# Audio.net
KiCad netlist of a schematic drawn in Altium Designer
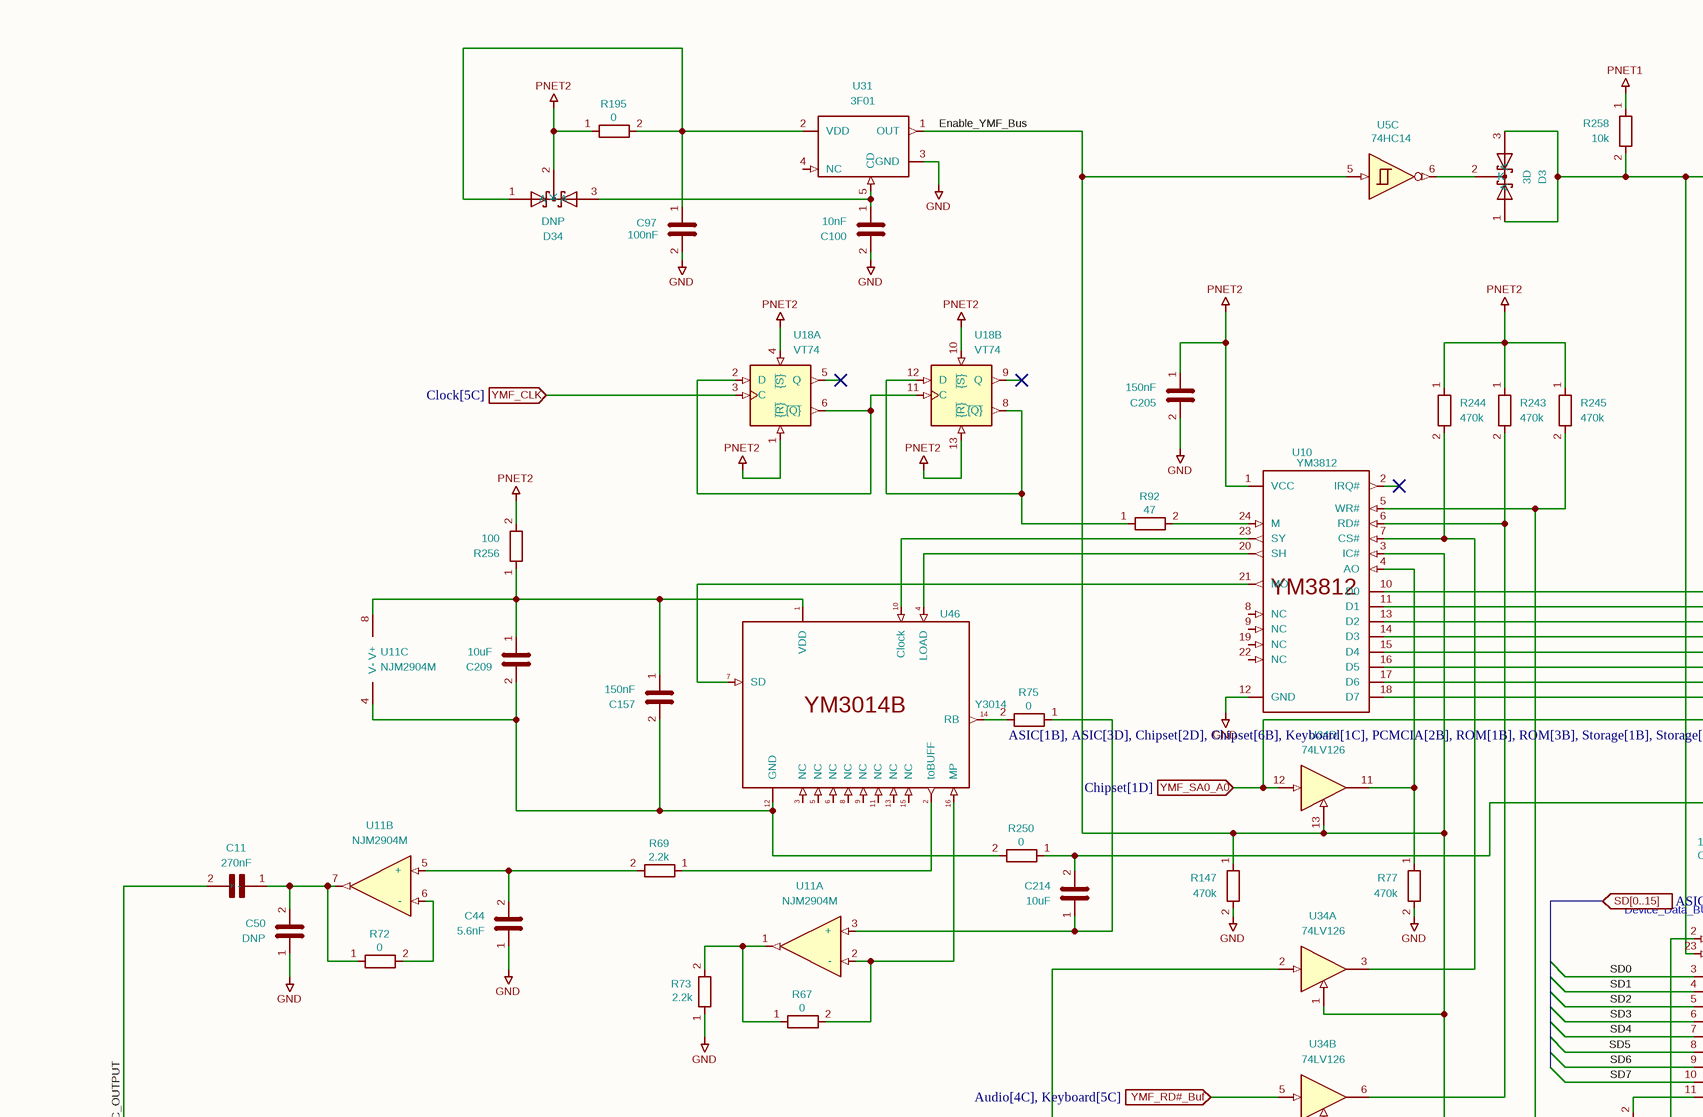
[diagram p0: Audio.SchDoc, top left]
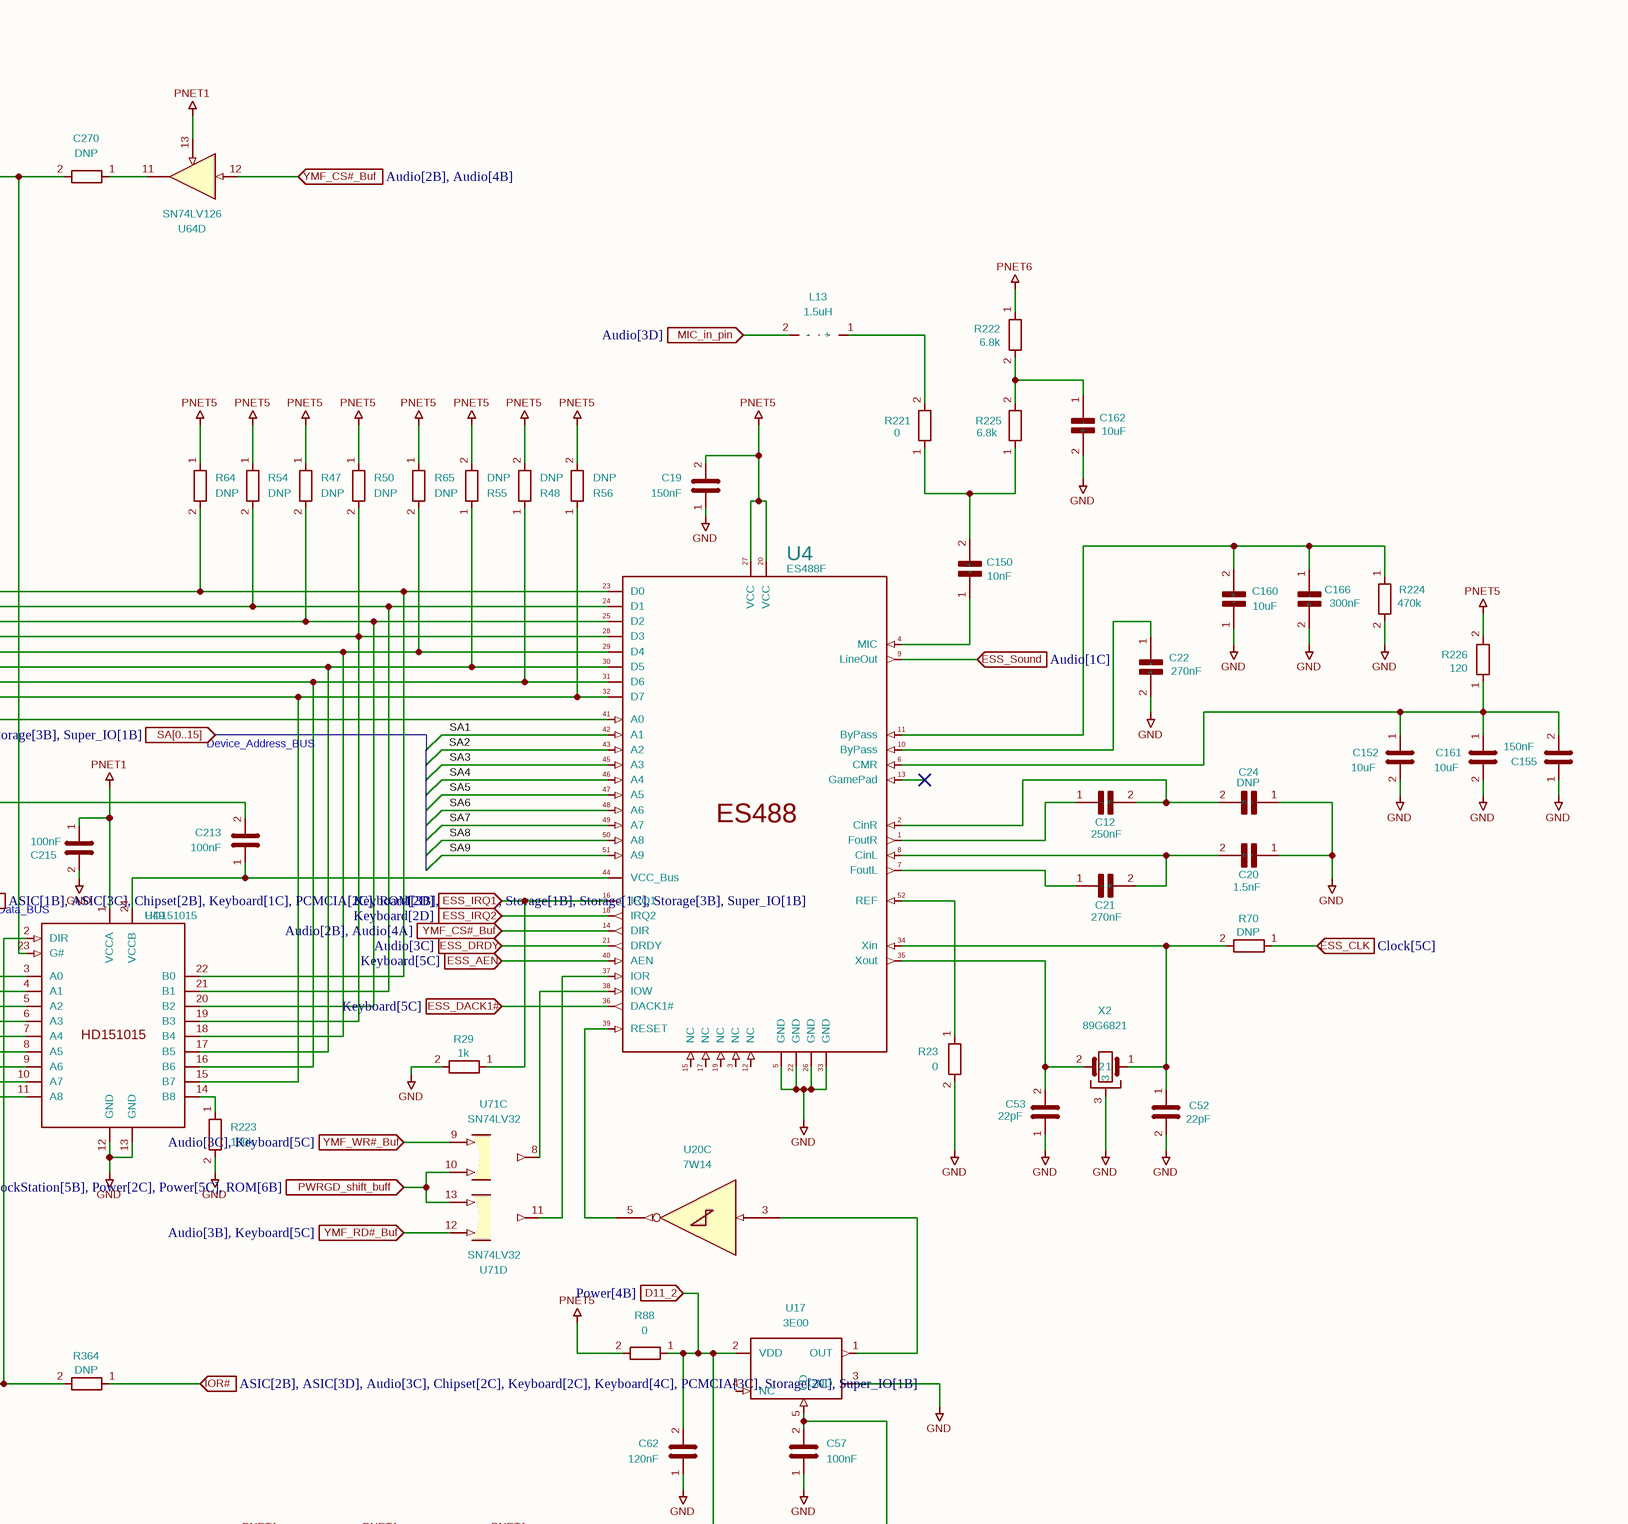
[diagram p1: Audio.SchDoc, top right]
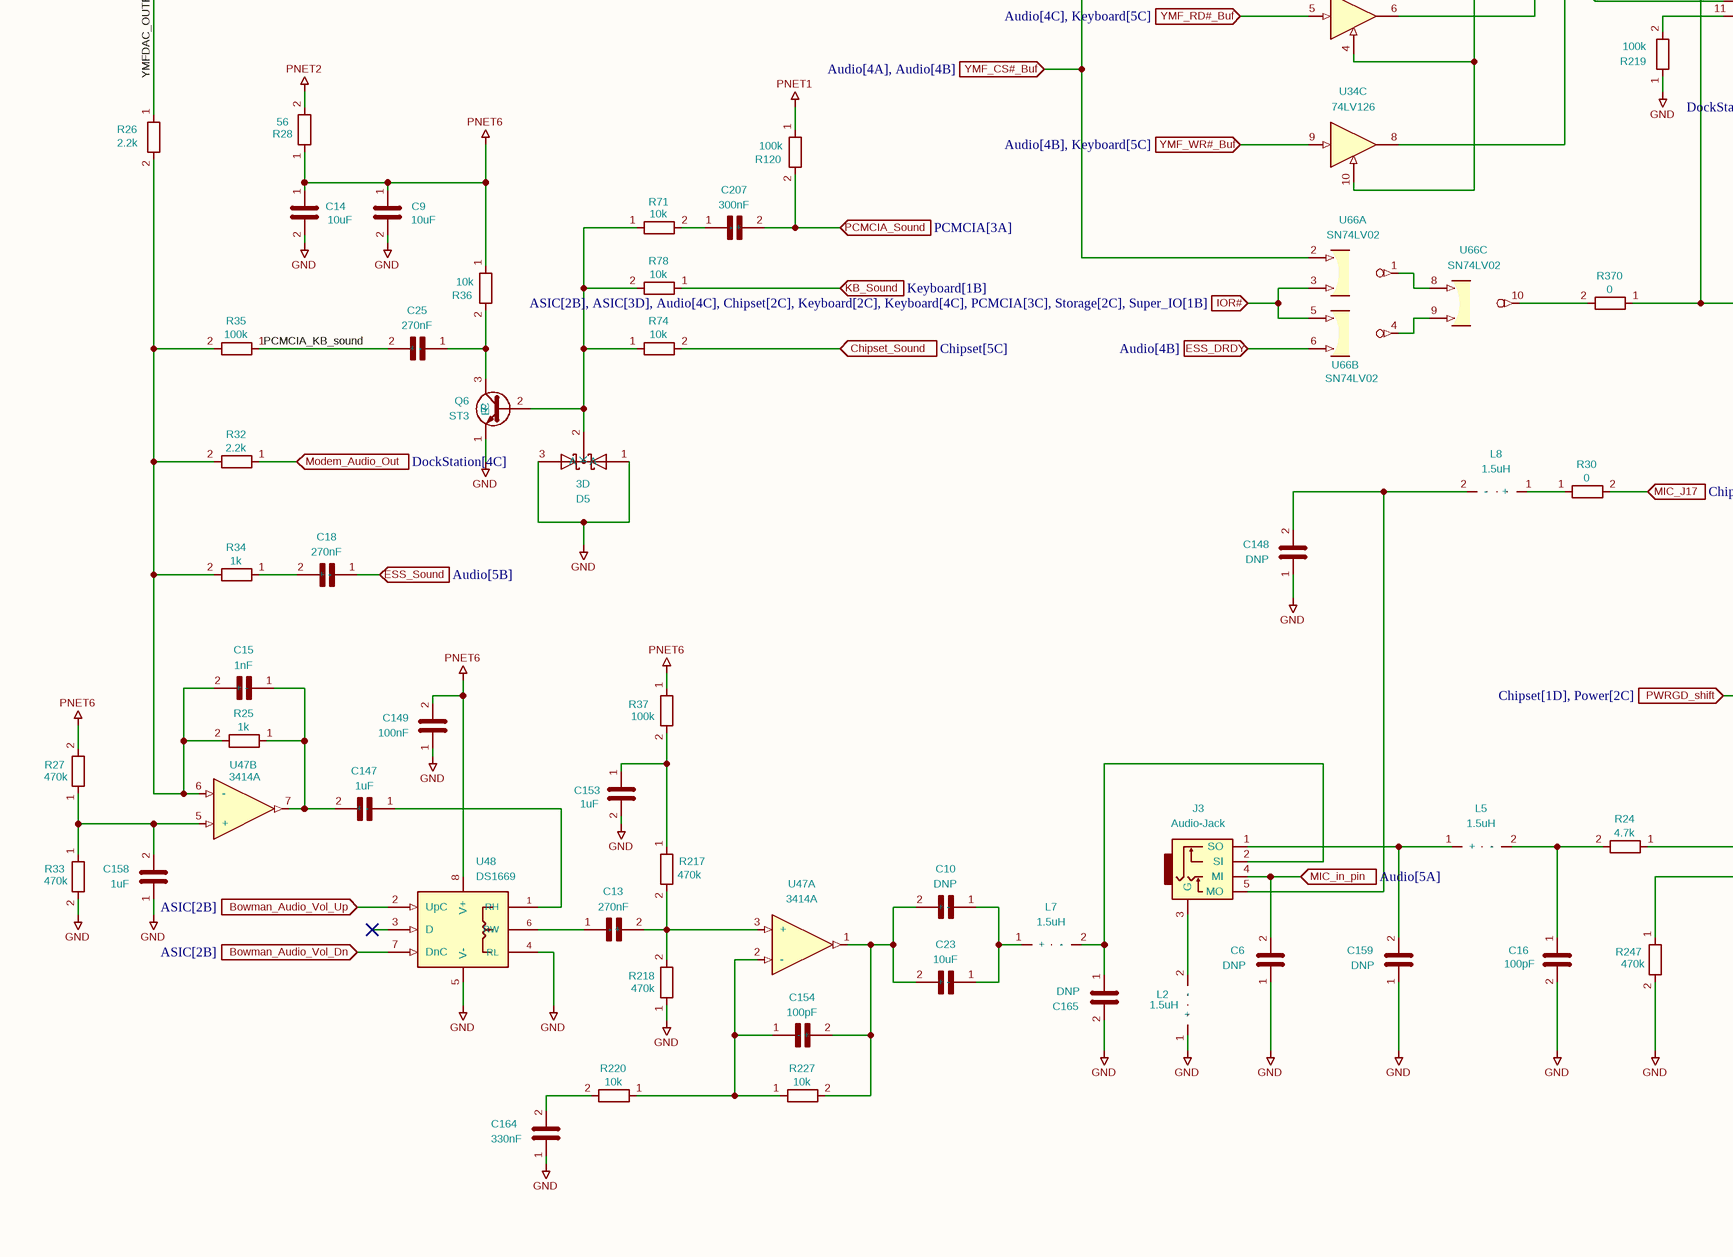
[diagram p2: Audio.SchDoc, bottom left]
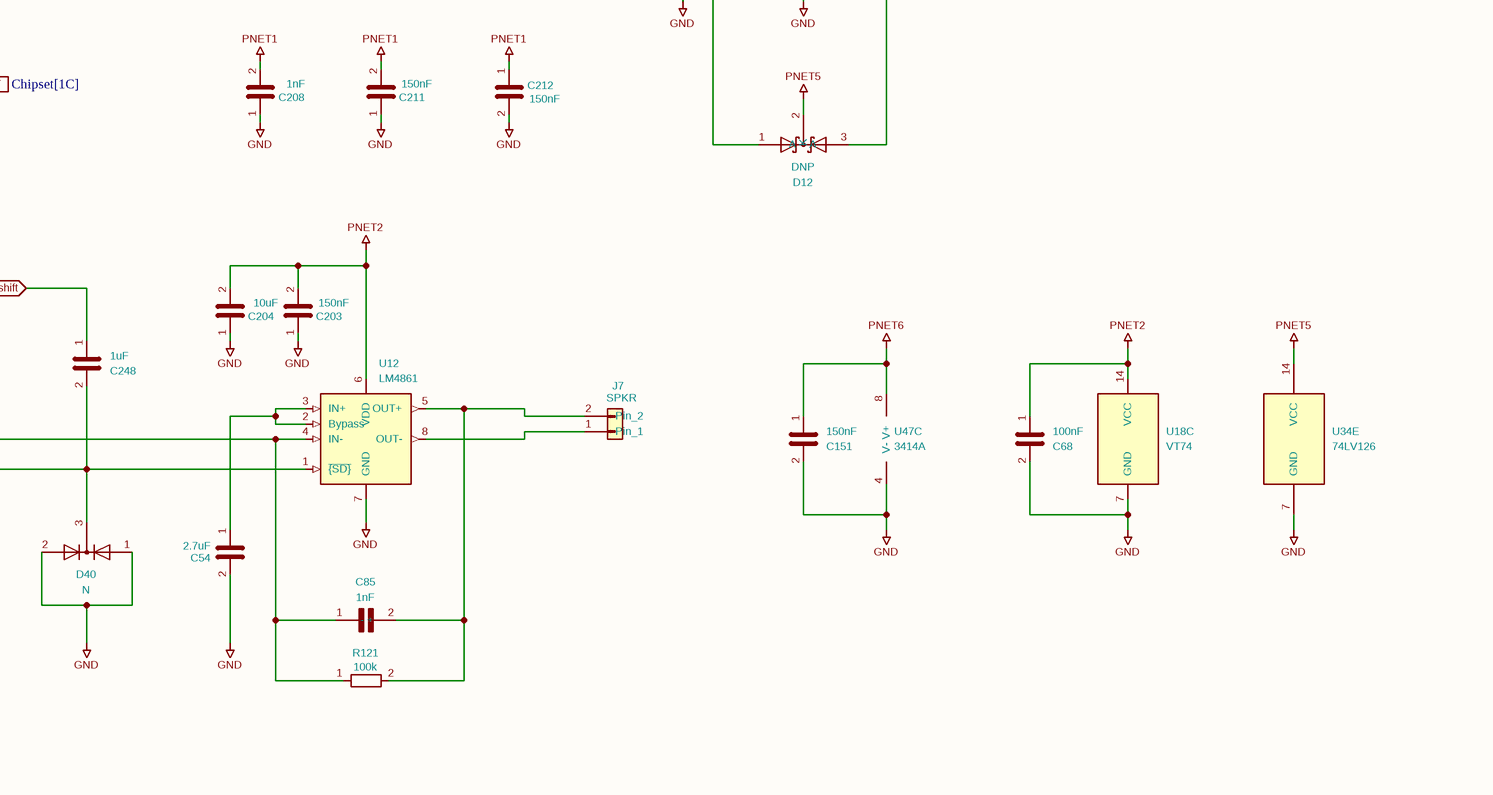
[diagram p3: Audio.SchDoc, bottom right]

(export (version "E")
  (design (tool "Eeschema 10.0.6"))
  (components
    (comp (ref "C6") (value "DNP") (footprint "C_0402_1005Metric") (libsource (lib "Device") (part "C")))
    (comp (ref "C9") (value "10uF") (footprint "C_1206_3216Metric") (libsource (lib "Device") (part "C")))
    (comp (ref "C10")
      (value "DNP")
      (footprint "C_1206_3216Metric")
      (libsource (lib "PCM_Elektuur") (part "C"))
    )
    (comp (ref "C11")
      (value "270nF")
      (footprint "C_0603_1608Metric")
      (libsource (lib "PCM_Elektuur") (part "C"))
    )
    (comp (ref "C12") (value "250nF") (footprint "C_0603_1608Metric") (libsource (lib "") (part "C_1")))
    (comp (ref "C13") (value "270nF") (footprint "C_0603_1608Metric") (libsource (lib "") (part "C_2")))
    (comp (ref "C14") (value "10uF") (footprint "C_1206_3216Metric") (libsource (lib "Device") (part "C")))
    (comp (ref "C15")
      (value "1nF")
      (footprint "C_0402_1005Metric")
      (libsource (lib "PCM_Elektuur") (part "C"))
    )
    (comp (ref "C16") (value "100pF") (footprint "C_0402_1005Metric") (libsource (lib "Device") (part "C")))
    (comp (ref "C18")
      (value "270nF")
      (footprint "C_0603_1608Metric")
      (libsource (lib "PCM_Elektuur") (part "C"))
    )
    (comp (ref "C19") (value "150nF") (footprint "C_0402_1005Metric") (libsource (lib "Device") (part "C")))
    (comp (ref "C20") (value "1.5nF") (footprint "C_0402_1005Metric") (libsource (lib "") (part "C_3")))
    (comp (ref "C21") (value "270nF") (footprint "C_0603_1608Metric") (libsource (lib "") (part "C_1")))
    (comp (ref "C22")
      (value "270nF")
      (footprint "C_0603_1608Metric")
      (libsource (lib "PCM_Elektuur") (part "C"))
    )
    (comp (ref "C23")
      (value "10uF")
      (footprint "C_1206_3216Metric")
      (libsource (lib "PCM_Elektuur") (part "C"))
    )
    (comp (ref "C24")
      (value "DNP")
      (footprint "C_0402_1005Metric")
      (libsource (lib "PCM_Elektuur") (part "C"))
    )
    (comp (ref "C25")
      (value "270nF")
      (footprint "C_0603_1608Metric")
      (libsource (lib "PCM_Elektuur") (part "C"))
    )
    (comp (ref "C44") (value "5.6nF") (footprint "C_0402_1005Metric") (libsource (lib "Device") (part "C")))
    (comp (ref "C50") (value "DNP") (footprint "C_0402_1005Metric") (libsource (lib "Device") (part "C")))
    (comp (ref "C52") (value "22pF") (footprint "C_0402_1005Metric") (libsource (lib "Device") (part "C")))
    (comp (ref "C53") (value "22pF") (footprint "C_0402_1005Metric") (libsource (lib "Device") (part "C")))
    (comp (ref "C54") (value "2.7uF") (footprint "C_0805_2012Metric") (libsource (lib "Device") (part "C")))
    (comp (ref "C57") (value "100nF") (footprint "C_0603_1608Metric") (libsource (lib "Device") (part "C")))
    (comp (ref "C62") (value "120nF") (footprint "C_0402_1005Metric") (libsource (lib "Device") (part "C")))
    (comp (ref "C68") (value "100nF") (footprint "C_0402_1005Metric") (libsource (lib "Device") (part "C")))
    (comp (ref "C85") (value "1nF") (footprint "C_0402_1005Metric") (libsource (lib "") (part "C_2")))
    (comp (ref "C97") (value "100nF") (footprint "C_0402_1005Metric") (libsource (lib "Device") (part "C")))
    (comp (ref "C100") (value "10nF") (footprint "C_0603_1608Metric") (libsource (lib "Device") (part "C")))
    (comp (ref "C147")
      (value "1uF")
      (footprint "C_0603_1608Metric")
      (libsource (lib "PCM_Elektuur") (part "C"))
    )
    (comp (ref "C148") (value "DNP") (footprint "C_0402_1005Metric") (libsource (lib "Device") (part "C")))
    (comp (ref "C149") (value "100nF") (footprint "C_0402_1005Metric") (libsource (lib "Device") (part "C")))
    (comp (ref "C150") (value "10nF") (footprint "C_0603_1608Metric") (libsource (lib "") (part "C_2")))
    (comp (ref "C151") (value "150nF") (footprint "C_0402_1005Metric") (libsource (lib "Device") (part "C")))
    (comp (ref "C152") (value "10uF") (footprint "C_1206_3216Metric") (libsource (lib "Device") (part "C")))
    (comp (ref "C153") (value "1uF") (footprint "C_0603_1608Metric") (libsource (lib "Device") (part "C")))
    (comp (ref "C154") (value "100pF") (footprint "C_0402_1005Metric") (libsource (lib "") (part "C_2")))
    (comp (ref "C155") (value "150nF") (footprint "C_0402_1005Metric") (libsource (lib "Device") (part "C")))
    (comp (ref "C157") (value "150nF") (footprint "C_0402_1005Metric") (libsource (lib "Device") (part "C")))
    (comp (ref "C158") (value "1uF") (footprint "C_0603_1608Metric") (libsource (lib "Device") (part "C")))
    (comp (ref "C159") (value "DNP") (footprint "C_0402_1005Metric") (libsource (lib "Device") (part "C")))
    (comp (ref "C160") (value "10uF") (footprint "C_1206_3216Metric") (libsource (lib "") (part "C_2")))
    (comp (ref "C161") (value "10uF") (footprint "C_1206_3216Metric") (libsource (lib "Device") (part "C")))
    (comp (ref "C162")
      (value "10uF")
      (footprint "C_1206_3216Metric")
      (libsource (lib "PCM_Elektuur") (part "C"))
    )
    (comp (ref "C164") (value "330nF") (footprint "C_0603_1608Metric") (libsource (lib "Device") (part "C")))
    (comp (ref "C165") (value "DNP") (footprint "C_0402_1005Metric") (libsource (lib "Device") (part "C")))
    (comp (ref "C166")
      (value "300nF")
      (footprint "C_0603_1608Metric")
      (libsource (lib "PCM_Elektuur") (part "C"))
    )
    (comp (ref "C203") (value "150nF") (footprint "C_0402_1005Metric") (libsource (lib "Device") (part "C")))
    (comp (ref "C204") (value "10uF") (footprint "C_1206_3216Metric") (libsource (lib "Device") (part "C")))
    (comp (ref "C205") (value "150nF") (footprint "C_0402_1005Metric") (libsource (lib "Device") (part "C")))
    (comp (ref "C207") (value "300nF") (footprint "C_0603_1608Metric") (libsource (lib "") (part "C_2")))
    (comp (ref "C208") (value "1nF") (footprint "C_0402_1005Metric") (libsource (lib "Device") (part "C")))
    (comp (ref "C209") (value "10uF") (footprint "C_1206_3216Metric") (libsource (lib "Device") (part "C")))
    (comp (ref "C211") (value "150nF") (footprint "C_0402_1005Metric") (libsource (lib "Device") (part "C")))
    (comp (ref "C212") (value "150nF") (footprint "C_0402_1005Metric") (libsource (lib "Device") (part "C")))
    (comp (ref "C213") (value "100nF") (footprint "C_0402_1005Metric") (libsource (lib "Device") (part "C")))
    (comp (ref "C214") (value "10uF") (footprint "C_1206_3216Metric") (libsource (lib "Device") (part "C")))
    (comp (ref "C215") (value "100nF") (footprint "C_0402_1005Metric") (libsource (lib "Device") (part "C")))
    (comp (ref "C248") (value "1uF") (footprint "C_0603_1608Metric") (libsource (lib "Device") (part "C")))
    (comp (ref "C270") (value "DNP") (footprint "C_0402_1005Metric") (libsource (lib "") (part "R_2")))
    (comp (ref "D3")
      (value "3D")
      (footprint "3D")
      (libsource (lib "Device") (part "D_Schottky_Dual_CommonCathode_AKA"))
    )
    (comp (ref "D5")
      (value "3D")
      (footprint "3D")
      (libsource (lib "Device") (part "D_Schottky_Dual_CommonCathode_AKA"))
    )
    (comp (ref "D12")
      (value "DNP")
      (footprint "3D")
      (libsource (lib "Device") (part "D_Schottky_Dual_CommonCathode_AKA"))
    )
    (comp (ref "D34")
      (value "DNP")
      (footprint "3D")
      (libsource (lib "Device") (part "D_Schottky_Dual_CommonCathode_AKA"))
    )
    (comp (ref "D40") (value "N") (footprint "SOT-416L") (libsource (lib "PC110") (part "3D_Diode")))
    (comp (ref "J3")
      (value "Audio-Jack")
      (footprint "Audio-Jack")
      (libsource (lib "PC110") (part "Audio_Jack"))
    )
    (comp (ref "J7")
      (value "SPKR")
      (footprint "SPKR")
      (libsource (lib "Connector_Generic") (part "Conn_01x02"))
    )
    (comp (ref "L2")
      (value "1.5uH")
      (footprint "L_0603_1608Metric")
      (libsource (lib "PCM_Elektuur") (part "L"))
    )
    (comp (ref "L5")
      (value "1.5uH")
      (footprint "L_0603_1608Metric")
      (libsource (lib "PCM_Elektuur") (part "L"))
    )
    (comp (ref "L7")
      (value "1.5uH")
      (footprint "L_0603_1608Metric")
      (libsource (lib "PCM_Elektuur") (part "L"))
    )
    (comp (ref "L8")
      (value "1.5uH")
      (footprint "L_0603_1608Metric")
      (libsource (lib "PCM_Elektuur") (part "L"))
    )
    (comp (ref "L13")
      (value "1.5uH")
      (footprint "L_0603_1608Metric")
      (libsource (lib "PCM_Elektuur") (part "L"))
    )
    (comp (ref "Q6")
      (value "ST3")
      (footprint "SOT-416L")
      (libsource (lib "PCM_Transistor_BJT_AKL") (part "Q_NPN_Generic_EBC"))
    )
    (comp (ref "R23") (value "0") (footprint "R_0402_1005Metric") (libsource (lib "") (part "R_1")))
    (comp (ref "R24") (value "4.7k") (footprint "R_0402_1005Metric") (libsource (lib "") (part "R_2")))
    (comp (ref "R25") (value "1k") (footprint "R_0402_1005Metric") (libsource (lib "") (part "R_2")))
    (comp (ref "R26") (value "2.2k") (footprint "R_0402_1005Metric") (libsource (lib "") (part "R_1")))
    (comp (ref "R27") (value "470k") (footprint "R_0402_1005Metric") (libsource (lib "Device") (part "R")))
    (comp (ref "R28") (value "56") (footprint "R_1206_3216Metric") (libsource (lib "Device") (part "R")))
    (comp (ref "R29") (value "1k") (footprint "R_0402_1005Metric") (libsource (lib "") (part "R_2")))
    (comp (ref "R30") (value "0") (footprint "R_0402_1005Metric") (libsource (lib "") (part "R_3")))
    (comp (ref "R32") (value "2.2k") (footprint "R_0402_1005Metric") (libsource (lib "") (part "R_2")))
    (comp (ref "R33") (value "470k") (footprint "R_0402_1005Metric") (libsource (lib "") (part "R_1")))
    (comp (ref "R34") (value "1k") (footprint "R_0402_1005Metric") (libsource (lib "") (part "R_2")))
    (comp (ref "R35") (value "100k") (footprint "R_0402_1005Metric") (libsource (lib "") (part "R_2")))
    (comp (ref "R36") (value "10k") (footprint "R_0402_1005Metric") (libsource (lib "") (part "R_1")))
    (comp (ref "R37") (value "100k") (footprint "R_0402_1005Metric") (libsource (lib "") (part "R_1")))
    (comp (ref "R47") (value "DNP") (footprint "R_0402_1005Metric") (libsource (lib "") (part "R_2")))
    (comp (ref "R48") (value "DNP") (footprint "R_0402_1005Metric") (libsource (lib "") (part "R_3")))
    (comp (ref "R50") (value "DNP") (footprint "R_0402_1005Metric") (libsource (lib "") (part "R_2")))
    (comp (ref "R54") (value "DNP") (footprint "R_0402_1005Metric") (libsource (lib "") (part "R_2")))
    (comp (ref "R55") (value "DNP") (footprint "R_0402_1005Metric") (libsource (lib "") (part "R_3")))
    (comp (ref "R56") (value "DNP") (footprint "R_0402_1005Metric") (libsource (lib "") (part "R_3")))
    (comp (ref "R64") (value "DNP") (footprint "R_0402_1005Metric") (libsource (lib "") (part "R_2")))
    (comp (ref "R65") (value "DNP") (footprint "R_0402_1005Metric") (libsource (lib "") (part "R_2")))
    (comp (ref "R67") (value "0") (footprint "R_0402_1005Metric") (libsource (lib "") (part "R_3")))
    (comp (ref "R69") (value "2.2k") (footprint "R_0402_1005Metric") (libsource (lib "") (part "R_2")))
    (comp (ref "R70") (value "DNP") (footprint "R_0402_1005Metric") (libsource (lib "") (part "R_2")))
    (comp (ref "R71") (value "10k") (footprint "R_0402_1005Metric") (libsource (lib "") (part "R_3")))
    (comp (ref "R72") (value "0") (footprint "R_0402_1005Metric") (libsource (lib "") (part "R_3")))
    (comp (ref "R73") (value "2.2k") (footprint "R_0402_1005Metric") (libsource (lib "Device") (part "R")))
    (comp (ref "R74") (value "10k") (footprint "R_0402_1005Metric") (libsource (lib "") (part "R_3")))
    (comp (ref "R75") (value "0") (footprint "R_0402_1005Metric") (libsource (lib "") (part "R_2")))
    (comp (ref "R77") (value "470k") (footprint "R_0402_1005Metric") (libsource (lib "") (part "R_1")))
    (comp (ref "R78") (value "10k") (footprint "R_0402_1005Metric") (libsource (lib "") (part "R_2")))
    (comp (ref "R88") (value "0") (footprint "R_0402_1005Metric") (libsource (lib "") (part "R_2")))
    (comp (ref "R92") (value "47") (footprint "R_0402_1005Metric") (libsource (lib "") (part "R_3")))
    (comp (ref "R120") (value "100k") (footprint "R_0402_1005Metric") (libsource (lib "") (part "R_1")))
    (comp (ref "R121") (value "100k") (footprint "R_0402_1005Metric") (libsource (lib "") (part "R_3")))
    (comp (ref "R147") (value "470k") (footprint "R_0402_1005Metric") (libsource (lib "") (part "R_1")))
    (comp (ref "R195") (value "0") (footprint "R_0402_1005Metric") (libsource (lib "") (part "R_3")))
    (comp (ref "R217") (value "470k") (footprint "R_0402_1005Metric") (libsource (lib "") (part "R_2")))
    (comp (ref "R218") (value "470k") (footprint "R_0402_1005Metric") (libsource (lib "Device") (part "R")))
    (comp (ref "R219") (value "100k") (footprint "R_0402_1005Metric") (libsource (lib "Device") (part "R")))
    (comp (ref "R220") (value "10k") (footprint "R_0402_1005Metric") (libsource (lib "") (part "R_2")))
    (comp (ref "R221") (value "0") (footprint "R_0402_1005Metric") (libsource (lib "Device") (part "R")))
    (comp (ref "R222") (value "6.8k") (footprint "R_0402_1005Metric") (libsource (lib "") (part "R_1")))
    (comp (ref "R223") (value "100k") (footprint "R_0402_1005Metric") (libsource (lib "") (part "R_2")))
    (comp (ref "R224") (value "470k") (footprint "R_0402_1005Metric") (libsource (lib "") (part "R_2")))
    (comp (ref "R225") (value "6.8k") (footprint "R_0402_1005Metric") (libsource (lib "Device") (part "R")))
    (comp (ref "R226") (value "120") (footprint "R_1206_3216Metric") (libsource (lib "Device") (part "R")))
    (comp (ref "R227") (value "10k") (footprint "R_0402_1005Metric") (libsource (lib "") (part "R_3")))
    (comp (ref "R243") (value "470k") (footprint "R_0402_1005Metric") (libsource (lib "") (part "R_2")))
    (comp (ref "R244") (value "470k") (footprint "R_0402_1005Metric") (libsource (lib "") (part "R_2")))
    (comp (ref "R245") (value "470k") (footprint "R_0402_1005Metric") (libsource (lib "") (part "R_2")))
    (comp (ref "R247") (value "470k") (footprint "R_0402_1005Metric") (libsource (lib "") (part "R_1")))
    (comp (ref "R250") (value "0") (footprint "R_0805_2012Metric") (libsource (lib "") (part "R_2")))
    (comp (ref "R256") (value "100") (footprint "R_0805_2012Metric") (libsource (lib "Device") (part "R")))
    (comp (ref "R258") (value "10k") (footprint "R_0402_1005Metric") (libsource (lib "") (part "R_1")))
    (comp (ref "R364") (value "DNP") (footprint "R_0402_1005Metric") (libsource (lib "") (part "R_2")))
    (comp (ref "R370") (value "0") (footprint "R_0402_1005Metric") (libsource (lib "") (part "R_2")))
    (comp (ref "U4") (value "ES488F") (footprint "QFN-52") (libsource (lib "PC110") (part "ES488")))
    (comp (ref "U5")
      (value "74HC14")
      (footprint "TSSOP-14_4.4x5mm_P0.65mm")
      (libsource (lib "74xx") (part "74LS14"))
    )
    (comp (ref "U10") (value "YM3812") (footprint "SOP-24") (libsource (lib "PC110") (part "YM3812")))
    (comp (ref "U11")
      (value "NJM2904M")
      (footprint "soic-8-small")
      (libsource (lib "Amplifier_Operational") (part "LM2904"))
    )
    (comp (ref "U12") (value "LM4861") (footprint "SOIC-8-narrow") (libsource (lib "PC110") (part "LM4861")))
    (comp (ref "U17") (value "3E00") (footprint "SOT-23-5") (libsource (lib "*") (part "QC01_1")))
    (comp (ref "U18")
      (value "VT74")
      (footprint "TSSOP-14_4.4x5mm_P0.65mm")
      (libsource (lib "74xx") (part "74HC74"))
    )
    (comp (ref "U20") (value "7W14") (footprint "sso-8") (libsource (lib "74xGxx") (part "74LVC3G14")))
    (comp (ref "U31") (value "3F01") (footprint "SOT-23-5") (libsource (lib "PC110") (part "QC01")))
    (comp (ref "U34")
      (value "74LV126")
      (footprint "TSSOP-14_4.4x5mm_P0.65mm")
      (libsource (lib "74xx") (part "74LS126"))
    )
    (comp (ref "U46") (value "Y3014") (footprint "SOP-16") (libsource (lib "PC110") (part "YM3014")))
    (comp (ref "U47") (value "3414A") (footprint "SOIC-8") (libsource (lib "Device") (part "Opamp_Dual")))
    (comp (ref "U48") (value "DS1669") (footprint "SOIC-8") (libsource (lib "PC110") (part "DS1669")))
    (comp (ref "U49")
      (value "HD151015")
      (footprint "SSOP-24_5.3x8.2mm_P0.65mm")
      (libsource (lib "PC110") (part "HD151015"))
    )
    (comp (ref "U64")
      (value "SN74LV126")
      (footprint "TSSOP-14_4.4x5mm_P0.65mm")
      (libsource (lib "") (part "74LS126_1"))
    )
    (comp (ref "U66")
      (value "SN74LV02")
      (footprint "TSSOP-14_4.4x5mm_P0.65mm")
      (libsource (lib "74xx") (part "74LS02"))
    )
    (comp (ref "U71")
      (value "SN74LV32")
      (footprint "TSSOP-14_4.4x5mm_P0.65mm")
      (libsource (lib "") (part "74LS32_1"))
    )
    (comp (ref "X2") (value "89G6821") (footprint "XTAL-1") (libsource (lib "Device") (part "Crystal_GND3")))
  )
  (nets
    (net (code "16") (name "/Bowman_Audio_Vol_Dn") (class "Default")
      (node (ref "U48") (pin "7") (pinfunction "DnC_7") (pintype "input"))
    )
    (net (code "17") (name "/Bowman_Audio_Vol_Up") (class "Default")
      (node (ref "U48") (pin "2") (pinfunction "UpC_2") (pintype "input"))
    )
    (net (code "18") (name "/Chipset_Sound") (class "Default")
      (node (ref "R74") (pin "2") (pinfunction "2_2") (pintype "passive"))
    )
    (net (code "19") (name "/D11_2") (class "Default")
      (node (ref "C62") (pin "2") (pinfunction "2_2") (pintype "passive"))
      (node (ref "D12") (pin "1") (pinfunction "A_1") (pintype "passive"))
      (node (ref "R88") (pin "1") (pinfunction "1_1") (pintype "passive"))
      (node (ref "U17") (pin "2") (pinfunction "VDD_2") (pintype "power_in"))
    )
    (net (code "20") (name "/ESS_AEN") (class "Default")
      (node (ref "U4") (pin "40") (pinfunction "AEN_40") (pintype "input"))
    )
    (net (code "21") (name "/ESS_CLK") (class "Default")
      (node (ref "R70") (pin "1") (pinfunction "1_1") (pintype "passive"))
    )
    (net (code "22") (name "/ESS_DACK1#") (class "Default")
      (node (ref "U4") (pin "36") (pinfunction "DACK1#_36") (pintype "output"))
    )
    (net (code "23") (name "/ESS_DRDY") (class "Default")
      (node (ref "U4") (pin "21") (pinfunction "DRDY_21") (pintype "output"))
      (node (ref "U66") (pin "6") (pinfunction "6_6") (pintype "input"))
    )
    (net (code "24") (name "/ESS_IRQ1") (class "Default")
      (node (ref "R29") (pin "1") (pinfunction "1_1") (pintype "passive"))
      (node (ref "U4") (pin "16") (pinfunction "IRQ1_16") (pintype "output"))
    )
    (net (code "25") (name "/ESS_IRQ2") (class "Default")
      (node (ref "U4") (pin "18") (pinfunction "IRQ2_18") (pintype "output"))
    )
    (net (code "26") (name "/ESS_Sound") (class "Default")
      (node (ref "C18") (pin "1") (pinfunction "+_1") (pintype "passive"))
      (node (ref "U4") (pin "9") (pinfunction "LineOut_9") (pintype "output"))
    )
    (net (code "27") (name "/Enable_YMF_Bus") (class "Default")
      (node (ref "R147") (pin "1") (pinfunction "1_1") (pintype "passive"))
      (node (ref "U10") (pin "3") (pinfunction "IC#_3") (pintype "input"))
      (node (ref "U31") (pin "1") (pinfunction "OUT_1") (pintype "output"))
      (node (ref "U34") (pin "1") (pinfunction "1_1") (pintype "input"))
      (node (ref "U34") (pin "10") (pinfunction "10_10") (pintype "input"))
      (node (ref "U34") (pin "13") (pinfunction "13_13") (pintype "input"))
      (node (ref "U34") (pin "4") (pinfunction "4_4") (pintype "input"))
      (node (ref "U5") (pin "5") (pinfunction "5_5") (pintype "input"))
    )
    (net (code "28") (name "/IOR#") (class "Default")
      (node (ref "R364") (pin "1") (pinfunction "1_1") (pintype "passive"))
      (node (ref "U66") (pin "3") (pinfunction "3_3") (pintype "input"))
      (node (ref "U66") (pin "5") (pinfunction "5_5") (pintype "input"))
    )
    (net (code "29") (name "/KB_Sound") (class "Default")
      (node (ref "R78") (pin "1") (pinfunction "1_1") (pintype "passive"))
    )
    (net (code "30") (name "/MIC_J17") (class "Default")
      (node (ref "R30") (pin "2") (pinfunction "2_2") (pintype "passive"))
    )
    (net (code "31") (name "/MIC_in_pin") (class "Default")
      (node (ref "C6") (pin "2") (pinfunction "2_2") (pintype "passive"))
      (node (ref "J3") (pin "4") (pinfunction "MI_4") (pintype "passive"))
      (node (ref "L13") (pin "2") (pinfunction "-_2") (pintype "passive"))
    )
    (net (code "32") (name "/Modem_Audio_Out") (class "Default")
      (node (ref "R32") (pin "1") (pinfunction "1_1") (pintype "passive"))
    )
    (net (code "33") (name "/PCMCIA_KB_sound") (class "Default")
      (node (ref "C25") (pin "2") (pinfunction "-_2") (pintype "passive"))
      (node (ref "R35") (pin "1") (pinfunction "1_1") (pintype "passive"))
    )
    (net (code "34") (name "/PCMCIA_Sound") (class "Default")
      (node (ref "C207") (pin "2") (pinfunction "-_2") (pintype "passive"))
      (node (ref "R120") (pin "2") (pinfunction "2_2") (pintype "passive"))
    )
    (net (code "35") (name "/PWRGD_shift") (class "Default")
      (node (ref "C248") (pin "1") (pinfunction "1_1") (pintype "passive"))
    )
    (net (code "36") (name "/PWRGD_shift_buff") (class "Default")
      (node (ref "U71") (pin "10") (pinfunction "10_10") (pintype "input"))
      (node (ref "U71") (pin "13") (pinfunction "13_13") (pintype "input"))
    )
    (net (code "37") (name "/SA1") (class "Default")
      (node (ref "U4") (pin "42") (pinfunction "A1_42") (pintype "input"))
    )
    (net (code "38") (name "/SA2") (class "Default")
      (node (ref "U4") (pin "43") (pinfunction "A2_43") (pintype "input"))
    )
    (net (code "39") (name "/SA3") (class "Default")
      (node (ref "U4") (pin "45") (pinfunction "A3_45") (pintype "input"))
    )
    (net (code "40") (name "/SA4") (class "Default")
      (node (ref "U4") (pin "46") (pinfunction "A4_46") (pintype "input"))
    )
    (net (code "41") (name "/SA5") (class "Default")
      (node (ref "U4") (pin "47") (pinfunction "A5_47") (pintype "input"))
    )
    (net (code "42") (name "/SA6") (class "Default")
      (node (ref "U4") (pin "48") (pinfunction "A6_48") (pintype "input"))
    )
    (net (code "43") (name "/SA7") (class "Default")
      (node (ref "U4") (pin "49") (pinfunction "A7_49") (pintype "input"))
    )
    (net (code "44") (name "/SA8") (class "Default")
      (node (ref "U4") (pin "50") (pinfunction "A8_50") (pintype "input"))
    )
    (net (code "45") (name "/SA9") (class "Default")
      (node (ref "U4") (pin "51") (pinfunction "A9_51") (pintype "input"))
    )
    (net (code "47") (name "/SD0") (class "Default")
      (node (ref "U49") (pin "3") (pinfunction "A0_3") (pintype "bidirectional"))
    )
    (net (code "48") (name "/SD1") (class "Default")
      (node (ref "U49") (pin "4") (pinfunction "A1_4") (pintype "bidirectional"))
    )
    (net (code "49") (name "/SD2") (class "Default")
      (node (ref "U49") (pin "5") (pinfunction "A2_5") (pintype "bidirectional"))
    )
    (net (code "50") (name "/SD3") (class "Default")
      (node (ref "U49") (pin "6") (pinfunction "A3_6") (pintype "bidirectional"))
    )
    (net (code "51") (name "/SD4") (class "Default")
      (node (ref "U49") (pin "7") (pinfunction "A4_7") (pintype "bidirectional"))
    )
    (net (code "52") (name "/SD5") (class "Default")
      (node (ref "U49") (pin "8") (pinfunction "A5_8") (pintype "bidirectional"))
    )
    (net (code "53") (name "/SD6") (class "Default")
      (node (ref "U49") (pin "9") (pinfunction "A6_9") (pintype "bidirectional"))
    )
    (net (code "54") (name "/SD7") (class "Default")
      (node (ref "U49") (pin "10") (pinfunction "A7_10") (pintype "bidirectional"))
    )
    (net (code "56") (name "/YMFDAC_OUTPUT") (class "Default")
      (node (ref "C11") (pin "2") (pinfunction "-_2") (pintype "passive"))
      (node (ref "R26") (pin "1") (pinfunction "1_1") (pintype "passive"))
    )
    (net (code "57") (name "/YMF_CLK") (class "Default")
      (node (ref "U18") (pin "3") (pinfunction "C_3") (pintype "input"))
    )
    (net (code "58") (name "/YMF_CS#_Buf") (class "Default")
      (node (ref "U34") (pin "2") (pinfunction "2_2") (pintype "input"))
      (node (ref "U4") (pin "14") (pinfunction "DIR_14") (pintype "output"))
      (node (ref "U64") (pin "12") (pinfunction "12_12") (pintype "input"))
      (node (ref "U66") (pin "2") (pinfunction "2_2") (pintype "input"))
    )
    (net (code "59") (name "/YMF_RD#_Buf") (class "Default")
      (node (ref "U34") (pin "5") (pinfunction "5_5") (pintype "input"))
      (node (ref "U71") (pin "12") (pinfunction "12_12") (pintype "input"))
    )
    (net (code "60") (name "/YMF_SA0_A0") (class "Default")
      (node (ref "U34") (pin "12") (pinfunction "12_12") (pintype "input"))
      (node (ref "U4") (pin "41") (pinfunction "A0_41") (pintype "input"))
    )
    (net (code "61") (name "/YMF_WR#_Buf") (class "Default")
      (node (ref "U34") (pin "9") (pinfunction "9_9") (pintype "input"))
      (node (ref "U71") (pin "9") (pinfunction "9_9") (pintype "input"))
    )
    (net (code "62") (name "GND") (class "Default")
      (node (ref "C100") (pin "2") (pinfunction "2_2") (pintype "passive"))
      (node (ref "C14") (pin "2") (pinfunction "2_2") (pintype "passive"))
      (node (ref "C148") (pin "1") (pinfunction "1_1") (pintype "passive"))
      (node (ref "C149") (pin "1") (pinfunction "1_1") (pintype "passive"))
      (node (ref "C151") (pin "2") (pinfunction "2_2") (pintype "passive"))
      (node (ref "C152") (pin "2") (pinfunction "2_2") (pintype "passive"))
      (node (ref "C153") (pin "2") (pinfunction "2_2") (pintype "passive"))
      (node (ref "C155") (pin "1") (pinfunction "1_1") (pintype "passive"))
      (node (ref "C158") (pin "1") (pinfunction "1_1") (pintype "passive"))
      (node (ref "C159") (pin "1") (pinfunction "1_1") (pintype "passive"))
      (node (ref "C16") (pin "2") (pinfunction "2_2") (pintype "passive"))
      (node (ref "C160") (pin "1") (pinfunction "+_1") (pintype "passive"))
      (node (ref "C161") (pin "2") (pinfunction "2_2") (pintype "passive"))
      (node (ref "C162") (pin "2") (pinfunction "-_2") (pintype "passive"))
      (node (ref "C164") (pin "1") (pinfunction "1_1") (pintype "passive"))
      (node (ref "C165") (pin "2") (pinfunction "2_2") (pintype "passive"))
      (node (ref "C166") (pin "2") (pinfunction "-_2") (pintype "passive"))
      (node (ref "C19") (pin "1") (pinfunction "1_1") (pintype "passive"))
      (node (ref "C20") (pin "1") (pinfunction "+_1") (pintype "passive"))
      (node (ref "C203") (pin "1") (pinfunction "1_1") (pintype "passive"))
      (node (ref "C204") (pin "1") (pinfunction "1_1") (pintype "passive"))
      (node (ref "C205") (pin "2") (pinfunction "2_2") (pintype "passive"))
      (node (ref "C208") (pin "1") (pinfunction "1_1") (pintype "passive"))
      (node (ref "C211") (pin "1") (pinfunction "1_1") (pintype "passive"))
      (node (ref "C212") (pin "2") (pinfunction "2_2") (pintype "passive"))
      (node (ref "C215") (pin "2") (pinfunction "2_2") (pintype "passive"))
      (node (ref "C22") (pin "2") (pinfunction "-_2") (pintype "passive"))
      (node (ref "C24") (pin "1") (pinfunction "+_1") (pintype "passive"))
      (node (ref "C44") (pin "1") (pinfunction "1_1") (pintype "passive"))
      (node (ref "C50") (pin "1") (pinfunction "1_1") (pintype "passive"))
      (node (ref "C52") (pin "2") (pinfunction "2_2") (pintype "passive"))
      (node (ref "C53") (pin "1") (pinfunction "1_1") (pintype "passive"))
      (node (ref "C54") (pin "2") (pinfunction "2_2") (pintype "passive"))
      (node (ref "C57") (pin "1") (pinfunction "1_1") (pintype "passive"))
      (node (ref "C6") (pin "1") (pinfunction "1_1") (pintype "passive"))
      (node (ref "C62") (pin "1") (pinfunction "1_1") (pintype "passive"))
      (node (ref "C68") (pin "2") (pinfunction "2_2") (pintype "passive"))
      (node (ref "C9") (pin "2") (pinfunction "2_2") (pintype "passive"))
      (node (ref "C97") (pin "2") (pinfunction "2_2") (pintype "passive"))
      (node (ref "D40") (pin "1") (pinfunction "1_1") (pintype "passive"))
      (node (ref "D40") (pin "2") (pinfunction "2_2") (pintype "passive"))
      (node (ref "D5") (pin "1") (pinfunction "A_1") (pintype "passive"))
      (node (ref "D5") (pin "3") (pinfunction "A_3") (pintype "passive"))
      (node (ref "L2") (pin "1") (pinfunction "+_1") (pintype "passive"))
      (node (ref "Q6") (pin "1") (pinfunction "E_1") (pintype "passive"))
      (node (ref "R147") (pin "2") (pinfunction "2_2") (pintype "passive"))
      (node (ref "R218") (pin "1") (pinfunction "1_1") (pintype "passive"))
      (node (ref "R219") (pin "1") (pinfunction "1_1") (pintype "passive"))
      (node (ref "R223") (pin "2") (pinfunction "2_2") (pintype "passive"))
      (node (ref "R224") (pin "2") (pinfunction "2_2") (pintype "passive"))
      (node (ref "R23") (pin "2") (pinfunction "2_2") (pintype "passive"))
      (node (ref "R247") (pin "2") (pinfunction "2_2") (pintype "passive"))
      (node (ref "R29") (pin "2") (pinfunction "2_2") (pintype "passive"))
      (node (ref "R33") (pin "2") (pinfunction "2_2") (pintype "passive"))
      (node (ref "R73") (pin "1") (pinfunction "1_1") (pintype "passive"))
      (node (ref "R77") (pin "2") (pinfunction "2_2") (pintype "passive"))
      (node (ref "U10") (pin "12") (pinfunction "GND_12") (pintype "power_in"))
      (node (ref "U12") (pin "7") (pinfunction "GND_7") (pintype "power_in"))
      (node (ref "U17") (pin "3") (pinfunction "GND_3") (pintype "power_in"))
      (node (ref "U18") (pin "7") (pinfunction "GND_7") (pintype "power_in"))
      (node (ref "U31") (pin "3") (pinfunction "GND_3") (pintype "power_in"))
      (node (ref "U34") (pin "7") (pinfunction "GND_7") (pintype "power_in"))
      (node (ref "U4") (pin "22") (pinfunction "GND_22") (pintype "power_in"))
      (node (ref "U4") (pin "26") (pinfunction "GND_26") (pintype "power_in"))
      (node (ref "U4") (pin "33") (pinfunction "GND_33") (pintype "power_in"))
      (node (ref "U4") (pin "5") (pinfunction "GND_5") (pintype "power_in"))
      (node (ref "U47") (pin "4") (pinfunction "V-_4") (pintype "power_in"))
      (node (ref "U48") (pin "4") (pinfunction "RL_4") (pintype "passive"))
      (node (ref "U48") (pin "5") (pinfunction "V-_5") (pintype "power_in"))
      (node (ref "U49") (pin "12") (pinfunction "GND_12") (pintype "power_in"))
      (node (ref "U49") (pin "13") (pinfunction "GND_13") (pintype "power_in"))
      (node (ref "X2") (pin "3") (pinfunction "3_3") (pintype "passive"))
    )
    (net (code "63") (name "Net-(C10-+)") (class "Default")
      (node (ref "C10") (pin "1") (pinfunction "+_1") (pintype "passive"))
      (node (ref "C23") (pin "1") (pinfunction "+_1") (pintype "passive"))
      (node (ref "L7") (pin "1") (pinfunction "+_1") (pintype "passive"))
    )
    (net (code "64") (name "Net-(C10--)") (class "Default")
      (node (ref "C10") (pin "2") (pinfunction "-_2") (pintype "passive"))
      (node (ref "C154") (pin "2") (pinfunction "-_2") (pintype "passive"))
      (node (ref "C23") (pin "2") (pinfunction "-_2") (pintype "passive"))
      (node (ref "R227") (pin "2") (pinfunction "2_2") (pintype "passive"))
      (node (ref "U47") (pin "1") (pinfunction "1_1") (pintype "output"))
    )
    (net (code "65") (name "Net-(C11-+)") (class "Default")
      (node (ref "C11") (pin "1") (pinfunction "+_1") (pintype "passive"))
      (node (ref "C50") (pin "2") (pinfunction "2_2") (pintype "passive"))
      (node (ref "R72") (pin "1") (pinfunction "1_1") (pintype "passive"))
      (node (ref "U11") (pin "7") (pinfunction "7_7") (pintype "output"))
    )
    (net (code "66") (name "Net-(C12-+)") (class "Default")
      (node (ref "C12") (pin "1") (pinfunction "+_1") (pintype "passive"))
      (node (ref "U4") (pin "1") (pinfunction "FoutR_1") (pintype "output"))
    )
    (net (code "67") (name "Net-(C12--)") (class "Default")
      (node (ref "C12") (pin "2") (pinfunction "-_2") (pintype "passive"))
      (node (ref "C24") (pin "2") (pinfunction "-_2") (pintype "passive"))
      (node (ref "U4") (pin "2") (pinfunction "CinR_2") (pintype "input"))
    )
    (net (code "68") (name "Net-(C13-+)") (class "Default")
      (node (ref "C13") (pin "1") (pinfunction "+_1") (pintype "passive"))
      (node (ref "U48") (pin "6") (pinfunction "RW_6") (pintype "passive"))
    )
    (net (code "69") (name "Net-(C13--)") (class "Default")
      (node (ref "C13") (pin "2") (pinfunction "-_2") (pintype "passive"))
      (node (ref "R217") (pin "2") (pinfunction "2_2") (pintype "passive"))
      (node (ref "R218") (pin "2") (pinfunction "2_2") (pintype "passive"))
      (node (ref "U47") (pin "3") (pinfunction "+_3") (pintype "input"))
    )
    (net (code "70") (name "Net-(C15--)") (class "Default")
      (node (ref "C15") (pin "2") (pinfunction "-_2") (pintype "passive"))
      (node (ref "R25") (pin "2") (pinfunction "2_2") (pintype "passive"))
      (node (ref "R26") (pin "2") (pinfunction "2_2") (pintype "passive"))
      (node (ref "R32") (pin "2") (pinfunction "2_2") (pintype "passive"))
      (node (ref "R34") (pin "2") (pinfunction "2_2") (pintype "passive"))
      (node (ref "R35") (pin "2") (pinfunction "2_2") (pintype "passive"))
      (node (ref "U47") (pin "6") (pinfunction "-_6") (pintype "input"))
    )
    (net (code "71") (name "Net-(C18--)") (class "Default")
      (node (ref "C18") (pin "2") (pinfunction "-_2") (pintype "passive"))
      (node (ref "R34") (pin "1") (pinfunction "1_1") (pintype "passive"))
    )
    (net (code "72") (name "Net-(C20--)") (class "Default")
      (node (ref "C20") (pin "2") (pinfunction "-_2") (pintype "passive"))
      (node (ref "C21") (pin "2") (pinfunction "-_2") (pintype "passive"))
      (node (ref "U4") (pin "8") (pinfunction "CinL_8") (pintype "input"))
    )
    (net (code "73") (name "Net-(C21-+)") (class "Default")
      (node (ref "C21") (pin "1") (pinfunction "+_1") (pintype "passive"))
      (node (ref "U4") (pin "7") (pinfunction "FoutL_7") (pintype "output"))
    )
    (net (code "74") (name "Net-(C22-+)") (class "Default")
      (node (ref "C22") (pin "1") (pinfunction "+_1") (pintype "passive"))
      (node (ref "U4") (pin "10") (pinfunction "ByPass_10") (pintype "input"))
    )
    (net (code "75") (name "Net-(C25-+)") (class "Default")
      (node (ref "C25") (pin "1") (pinfunction "+_1") (pintype "passive"))
      (node (ref "Q6") (pin "3") (pinfunction "C_3") (pintype "passive"))
      (node (ref "R36") (pin "2") (pinfunction "2_2") (pintype "passive"))
    )
    (net (code "76") (name "Net-(C85-+)") (class "Default")
      (node (ref "C85") (pin "1") (pinfunction "+_1") (pintype "passive"))
      (node (ref "R121") (pin "1") (pinfunction "1_1") (pintype "passive"))
      (node (ref "R24") (pin "1") (pinfunction "1_1") (pintype "passive"))
      (node (ref "U12") (pin "4") (pinfunction "IN-_4") (pintype "input"))
    )
    (net (code "77") (name "Net-(C85--)") (class "Default")
      (node (ref "C85") (pin "2") (pinfunction "-_2") (pintype "passive"))
      (node (ref "J7") (pin "2") (pinfunction "Pin_2_2") (pintype "passive"))
      (node (ref "R121") (pin "2") (pinfunction "2_2") (pintype "passive"))
      (node (ref "U12") (pin "5") (pinfunction "OUT+_5") (pintype "output"))
    )
    (net (code "78") (name "Net-(C147-+)") (class "Default")
      (node (ref "C147") (pin "1") (pinfunction "+_1") (pintype "passive"))
      (node (ref "U48") (pin "1") (pinfunction "RH_1") (pintype "passive"))
    )
    (net (code "79") (name "Net-(C147--)") (class "Default")
      (node (ref "C147") (pin "2") (pinfunction "-_2") (pintype "passive"))
      (node (ref "C15") (pin "1") (pinfunction "+_1") (pintype "passive"))
      (node (ref "R25") (pin "1") (pinfunction "1_1") (pintype "passive"))
      (node (ref "U47") (pin "7") (pinfunction "7_7") (pintype "output"))
    )
    (net (code "80") (name "Net-(C150-+)") (class "Default")
      (node (ref "C150") (pin "1") (pinfunction "+_1") (pintype "passive"))
      (node (ref "U4") (pin "4") (pinfunction "MIC_4") (pintype "input"))
    )
    (net (code "81") (name "Net-(C150--)") (class "Default")
      (node (ref "C150") (pin "2") (pinfunction "-_2") (pintype "passive"))
      (node (ref "R221") (pin "1") (pinfunction "1_1") (pintype "passive"))
      (node (ref "R225") (pin "1") (pinfunction "1_1") (pintype "passive"))
    )
    (net (code "82") (name "Net-(C153-Pad1)") (class "Default")
      (node (ref "C153") (pin "1") (pinfunction "1_1") (pintype "passive"))
      (node (ref "R217") (pin "1") (pinfunction "1_1") (pintype "passive"))
      (node (ref "R37") (pin "2") (pinfunction "2_2") (pintype "passive"))
    )
    (net (code "83") (name "Net-(C154-+)") (class "Default")
      (node (ref "C154") (pin "1") (pinfunction "+_1") (pintype "passive"))
      (node (ref "R220") (pin "1") (pinfunction "1_1") (pintype "passive"))
      (node (ref "R227") (pin "1") (pinfunction "1_1") (pintype "passive"))
      (node (ref "U47") (pin "2") (pinfunction "-_2") (pintype "input"))
    )
    (net (code "84") (name "Net-(C160--)") (class "Default")
      (node (ref "C160") (pin "2") (pinfunction "-_2") (pintype "passive"))
      (node (ref "C166") (pin "1") (pinfunction "+_1") (pintype "passive"))
      (node (ref "R224") (pin "1") (pinfunction "1_1") (pintype "passive"))
      (node (ref "U4") (pin "11") (pinfunction "ByPass_11") (pintype "input"))
    )
    (net (code "85") (name "Net-(C162-+)") (class "Default")
      (node (ref "C162") (pin "1") (pinfunction "+_1") (pintype "passive"))
      (node (ref "R222") (pin "2") (pinfunction "2_2") (pintype "passive"))
      (node (ref "R225") (pin "2") (pinfunction "2_2") (pintype "passive"))
    )
    (net (code "86") (name "Net-(C164-Pad2)") (class "Default")
      (node (ref "C164") (pin "2") (pinfunction "2_2") (pintype "passive"))
      (node (ref "R220") (pin "2") (pinfunction "2_2") (pintype "passive"))
    )
    (net (code "87") (name "Net-(C207-+)") (class "Default")
      (node (ref "C207") (pin "1") (pinfunction "+_1") (pintype "passive"))
      (node (ref "R71") (pin "2") (pinfunction "2_2") (pintype "passive"))
    )
    (net (code "88") (name "Net-(C213-Pad2)") (class "Default")
      (node (ref "C213") (pin "2") (pinfunction "2_2") (pintype "passive"))
      (node (ref "C214") (pin "2") (pinfunction "2_2") (pintype "passive"))
      (node (ref "R250") (pin "1") (pinfunction "1_1") (pintype "passive"))
    )
    (net (code "89") (name "Net-(C270-Pad1)") (class "Default")
      (node (ref "C270") (pin "1") (pinfunction "1_1") (pintype "passive"))
      (node (ref "U64") (pin "11") (pinfunction "11_11") (pintype "tri_state"))
    )
    (net (code "90") (name "Net-(D3-K)") (class "Default")
      (node (ref "D3") (pin "2") (pinfunction "K_2") (pintype "passive"))
      (node (ref "U5") (pin "6") (pinfunction "6_6") (pintype "output"))
    )
    (net (code "91") (name "Net-(D5-K)") (class "Default")
      (node (ref "D5") (pin "2") (pinfunction "K_2") (pintype "passive"))
      (node (ref "Q6") (pin "2") (pinfunction "B_2") (pintype "passive"))
      (node (ref "R71") (pin "1") (pinfunction "1_1") (pintype "passive"))
      (node (ref "R74") (pin "1") (pinfunction "1_1") (pintype "passive"))
      (node (ref "R78") (pin "2") (pinfunction "2_2") (pintype "passive"))
    )
    (net (code "92") (name "Net-(J3-G)") (class "Default")
      (node (ref "J3") (pin "3") (pinfunction "G_3") (pintype "passive"))
      (node (ref "L2") (pin "2") (pinfunction "-_2") (pintype "passive"))
    )
    (net (code "93") (name "Net-(J3-MO)") (class "Default")
      (node (ref "C148") (pin "2") (pinfunction "2_2") (pintype "passive"))
      (node (ref "J3") (pin "5") (pinfunction "MO_5") (pintype "passive"))
      (node (ref "L8") (pin "2") (pinfunction "-_2") (pintype "passive"))
    )
    (net (code "94") (name "Net-(J3-SI)") (class "Default")
      (node (ref "C165") (pin "1") (pinfunction "1_1") (pintype "passive"))
      (node (ref "J3") (pin "2") (pinfunction "SI_2") (pintype "passive"))
      (node (ref "L7") (pin "2") (pinfunction "-_2") (pintype "passive"))
    )
    (net (code "95") (name "Net-(J3-SO)") (class "Default")
      (node (ref "C159") (pin "2") (pinfunction "2_2") (pintype "passive"))
      (node (ref "J3") (pin "1") (pinfunction "SO_1") (pintype "passive"))
      (node (ref "L5") (pin "1") (pinfunction "+_1") (pintype "passive"))
    )
    (net (code "96") (name "Net-(J7-Pin_1)") (class "Default")
      (node (ref "J7") (pin "1") (pinfunction "Pin_1_1") (pintype "passive"))
      (node (ref "U12") (pin "8") (pinfunction "OUT-_8") (pintype "output"))
    )
    (net (code "97") (name "Net-(L5--)") (class "Default")
      (node (ref "C16") (pin "1") (pinfunction "1_1") (pintype "passive"))
      (node (ref "L5") (pin "2") (pinfunction "-_2") (pintype "passive"))
      (node (ref "R24") (pin "2") (pinfunction "2_2") (pintype "passive"))
    )
    (net (code "98") (name "Net-(L8-+)") (class "Default")
      (node (ref "L8") (pin "1") (pinfunction "+_1") (pintype "passive"))
      (node (ref "R30") (pin "1") (pinfunction "1_1") (pintype "passive"))
    )
    (net (code "99") (name "Net-(L13-+)") (class "Default")
      (node (ref "L13") (pin "1") (pinfunction "+_1") (pintype "passive"))
      (node (ref "R221") (pin "2") (pinfunction "2_2") (pintype "passive"))
    )
    (net (code "100") (name "Net-(R67-Pad1)") (class "Default")
      (node (ref "R67") (pin "1") (pinfunction "1_1") (pintype "passive"))
      (node (ref "R73") (pin "2") (pinfunction "2_2") (pintype "passive"))
      (node (ref "U11") (pin "1") (pinfunction "1_1") (pintype "output"))
    )
    (net (code "101") (name "Net-(R370-Pad2)") (class "Default")
      (node (ref "R370") (pin "2") (pinfunction "2_2") (pintype "passive"))
      (node (ref "U66") (pin "10") (pinfunction "10_10") (pintype "output"))
    )
    (net (code "102") (name "Net-(U4-CMR)") (class "Default")
      (node (ref "C152") (pin "1") (pinfunction "1_1") (pintype "passive"))
      (node (ref "C155") (pin "2") (pinfunction "2_2") (pintype "passive"))
      (node (ref "C161") (pin "1") (pinfunction "1_1") (pintype "passive"))
      (node (ref "R226") (pin "1") (pinfunction "1_1") (pintype "passive"))
      (node (ref "U4") (pin "6") (pinfunction "CMR_6") (pintype "input"))
    )
    (net (code "103") (name "Net-(U4-IOR)") (class "Default")
      (node (ref "U4") (pin "37") (pinfunction "IOR_37") (pintype "input"))
      (node (ref "U71") (pin "11") (pinfunction "11_11") (pintype "output"))
    )
    (net (code "104") (name "Net-(U4-IOW)") (class "Default")
      (node (ref "U4") (pin "38") (pinfunction "IOW_38") (pintype "input"))
      (node (ref "U71") (pin "8") (pinfunction "8_8") (pintype "output"))
    )
    (net (code "105") (name "Net-(U4-REF)") (class "Default")
      (node (ref "R23") (pin "1") (pinfunction "1_1") (pintype "passive"))
      (node (ref "U4") (pin "52") (pinfunction "REF_52") (pintype "input"))
    )
    (net (code "106") (name "Net-(U4-RESET)") (class "Default")
      (node (ref "U20") (pin "5") (pinfunction "5_5") (pintype "output"))
      (node (ref "U4") (pin "39") (pinfunction "RESET_39") (pintype "input"))
    )
    (net (code "107") (name "Net-(U4-VCC_Bus)") (class "Default")
      (node (ref "C213") (pin "1") (pinfunction "1_1") (pintype "passive"))
      (node (ref "U4") (pin "44") (pinfunction "VCC_Bus_44") (pintype "power_in"))
      (node (ref "U49") (pin "24") (pinfunction "VCCB_24") (pintype "power_in"))
    )
    (net (code "108") (name "Net-(U4-Xin)") (class "Default")
      (node (ref "C52") (pin "1") (pinfunction "1_1") (pintype "passive"))
      (node (ref "R70") (pin "2") (pinfunction "2_2") (pintype "passive"))
      (node (ref "U4") (pin "34") (pinfunction "Xin_34") (pintype "input"))
      (node (ref "X2") (pin "1") (pinfunction "1_1") (pintype "passive"))
    )
    (net (code "109") (name "Net-(U4-Xout)") (class "Default")
      (node (ref "C53") (pin "2") (pinfunction "2_2") (pintype "passive"))
      (node (ref "U4") (pin "35") (pinfunction "Xout_35") (pintype "output"))
      (node (ref "X2") (pin "2") (pinfunction "2_2") (pintype "passive"))
    )
    (net (code "110") (name "Net-(U10-AO)") (class "Default")
      (node (ref "R77") (pin "1") (pinfunction "1_1") (pintype "passive"))
      (node (ref "U10") (pin "4") (pinfunction "AO_4") (pintype "input"))
      (node (ref "U34") (pin "11") (pinfunction "11_11") (pintype "tri_state"))
    )
    (net (code "111") (name "Net-(U10-CS#)") (class "Default")
      (node (ref "R244") (pin "2") (pinfunction "2_2") (pintype "passive"))
      (node (ref "U10") (pin "7") (pinfunction "CS#_7") (pintype "input"))
      (node (ref "U34") (pin "3") (pinfunction "3_3") (pintype "tri_state"))
    )
    (net (code "112") (name "Net-(U10-D0)") (class "Default")
      (node (ref "R64") (pin "2") (pinfunction "2_2") (pintype "passive"))
      (node (ref "U10") (pin "10") (pinfunction "D0_10") (pintype "bidirectional"))
      (node (ref "U4") (pin "23") (pinfunction "D0_23") (pintype "bidirectional"))
      (node (ref "U49") (pin "22") (pinfunction "B0_22") (pintype "bidirectional"))
    )
    (net (code "113") (name "Net-(U10-D1)") (class "Default")
      (node (ref "R54") (pin "2") (pinfunction "2_2") (pintype "passive"))
      (node (ref "U10") (pin "11") (pinfunction "D1_11") (pintype "bidirectional"))
      (node (ref "U4") (pin "24") (pinfunction "D1_24") (pintype "bidirectional"))
      (node (ref "U49") (pin "21") (pinfunction "B1_21") (pintype "bidirectional"))
    )
    (net (code "114") (name "Net-(U10-D2)") (class "Default")
      (node (ref "R47") (pin "2") (pinfunction "2_2") (pintype "passive"))
      (node (ref "U10") (pin "13") (pinfunction "D2_13") (pintype "bidirectional"))
      (node (ref "U4") (pin "25") (pinfunction "D2_25") (pintype "bidirectional"))
      (node (ref "U49") (pin "20") (pinfunction "B2_20") (pintype "bidirectional"))
    )
    (net (code "115") (name "Net-(U10-D3)") (class "Default")
      (node (ref "R50") (pin "2") (pinfunction "2_2") (pintype "passive"))
      (node (ref "U10") (pin "14") (pinfunction "D3_14") (pintype "bidirectional"))
      (node (ref "U4") (pin "28") (pinfunction "D3_28") (pintype "bidirectional"))
      (node (ref "U49") (pin "19") (pinfunction "B3_19") (pintype "bidirectional"))
    )
    (net (code "116") (name "Net-(U10-D4)") (class "Default")
      (node (ref "R65") (pin "2") (pinfunction "2_2") (pintype "passive"))
      (node (ref "U10") (pin "15") (pinfunction "D4_15") (pintype "bidirectional"))
      (node (ref "U4") (pin "29") (pinfunction "D4_29") (pintype "bidirectional"))
      (node (ref "U49") (pin "18") (pinfunction "B4_18") (pintype "bidirectional"))
    )
    (net (code "117") (name "Net-(U10-D5)") (class "Default")
      (node (ref "R55") (pin "1") (pinfunction "1_1") (pintype "passive"))
      (node (ref "U10") (pin "16") (pinfunction "D5_16") (pintype "bidirectional"))
      (node (ref "U4") (pin "30") (pinfunction "D5_30") (pintype "bidirectional"))
      (node (ref "U49") (pin "17") (pinfunction "B5_17") (pintype "bidirectional"))
    )
    (net (code "118") (name "Net-(U10-D6)") (class "Default")
      (node (ref "R48") (pin "1") (pinfunction "1_1") (pintype "passive"))
      (node (ref "U10") (pin "17") (pinfunction "D6_17") (pintype "bidirectional"))
      (node (ref "U4") (pin "31") (pinfunction "D6_31") (pintype "bidirectional"))
      (node (ref "U49") (pin "16") (pinfunction "B6_16") (pintype "bidirectional"))
    )
    (net (code "119") (name "Net-(U10-D7)") (class "Default")
      (node (ref "R56") (pin "1") (pinfunction "1_1") (pintype "passive"))
      (node (ref "U10") (pin "18") (pinfunction "D7_18") (pintype "bidirectional"))
      (node (ref "U4") (pin "32") (pinfunction "D7_32") (pintype "bidirectional"))
      (node (ref "U49") (pin "15") (pinfunction "B7_15") (pintype "bidirectional"))
    )
    (net (code "120") (name "Net-(U10-M)") (class "Default")
      (node (ref "R92") (pin "2") (pinfunction "2_2") (pintype "passive"))
      (node (ref "U10") (pin "24") (pinfunction "M_24") (pintype "input"))
    )
    (net (code "121") (name "Net-(U10-MO)") (class "Default")
      (node (ref "U10") (pin "21") (pinfunction "MO_21") (pintype "output"))
      (node (ref "U46") (pin "7") (pinfunction "SD_7") (pintype "input"))
    )
    (net (code "122") (name "Net-(U10-RD#)") (class "Default")
      (node (ref "R243") (pin "2") (pinfunction "2_2") (pintype "passive"))
      (node (ref "U10") (pin "6") (pinfunction "RD#_6") (pintype "input"))
      (node (ref "U34") (pin "6") (pinfunction "6_6") (pintype "tri_state"))
    )
    (net (code "123") (name "Net-(U10-SH)") (class "Default")
      (node (ref "U10") (pin "20") (pinfunction "SH_20") (pintype "output"))
      (node (ref "U46") (pin "4") (pinfunction "LOAD_4") (pintype "input"))
    )
    (net (code "124") (name "Net-(U10-SY)") (class "Default")
      (node (ref "U10") (pin "23") (pinfunction "SY_23") (pintype "output"))
      (node (ref "U46") (pin "10") (pinfunction "Clock_10") (pintype "input"))
    )
    (net (code "125") (name "Net-(U10-WR#)") (class "Default")
      (node (ref "R245") (pin "2") (pinfunction "2_2") (pintype "passive"))
      (node (ref "U10") (pin "5") (pinfunction "WR#_5") (pintype "input"))
      (node (ref "U34") (pin "8") (pinfunction "8_8") (pintype "tri_state"))
    )
    (net (code "126") (name "Net-(U11A-+)") (class "Default")
      (node (ref "C214") (pin "1") (pinfunction "1_1") (pintype "passive"))
      (node (ref "R75") (pin "1") (pinfunction "1_1") (pintype "passive"))
      (node (ref "U11") (pin "3") (pinfunction "+_3") (pintype "input"))
    )
    (net (code "127") (name "Net-(U11A--)") (class "Default")
      (node (ref "R67") (pin "2") (pinfunction "2_2") (pintype "passive"))
      (node (ref "U11") (pin "2") (pinfunction "-_2") (pintype "input"))
      (node (ref "U46") (pin "16") (pinfunction "MP_16") (pintype "input"))
    )
    (net (code "128") (name "Net-(U11B-+)") (class "Default")
      (node (ref "C44") (pin "2") (pinfunction "2_2") (pintype "passive"))
      (node (ref "R69") (pin "2") (pinfunction "2_2") (pintype "passive"))
      (node (ref "U11") (pin "5") (pinfunction "+_5") (pintype "input"))
    )
    (net (code "129") (name "Net-(U11B--)") (class "Default")
      (node (ref "R72") (pin "2") (pinfunction "2_2") (pintype "passive"))
      (node (ref "U11") (pin "6") (pinfunction "-_6") (pintype "input"))
    )
    (net (code "130") (name "Net-(U11C-V+)") (class "Default")
      (node (ref "C157") (pin "1") (pinfunction "1_1") (pintype "passive"))
      (node (ref "C209") (pin "1") (pinfunction "1_1") (pintype "passive"))
      (node (ref "R256") (pin "1") (pinfunction "1_1") (pintype "passive"))
      (node (ref "U11") (pin "8") (pinfunction "V+_8") (pintype "power_in"))
      (node (ref "U46") (pin "1") (pinfunction "VDD_1") (pintype "power_in"))
    )
    (net (code "131") (name "Net-(U11C-V-)") (class "Default")
      (node (ref "C157") (pin "2") (pinfunction "2_2") (pintype "passive"))
      (node (ref "C209") (pin "2") (pinfunction "2_2") (pintype "passive"))
      (node (ref "R250") (pin "2") (pinfunction "2_2") (pintype "passive"))
      (node (ref "U11") (pin "4") (pinfunction "V-_4") (pintype "power_in"))
      (node (ref "U46") (pin "12") (pinfunction "GND_12") (pintype "power_in"))
    )
    (net (code "132") (name "Net-(U12-Bypass)") (class "Default")
      (node (ref "C54") (pin "1") (pinfunction "1_1") (pintype "passive"))
      (node (ref "U12") (pin "2") (pinfunction "Bypass_2") (pintype "input"))
      (node (ref "U12") (pin "3") (pinfunction "IN+_3") (pintype "input"))
    )
    (net (code "133") (name "Net-(U12-~{{SD}})") (class "Default")
      (node (ref "C248") (pin "2") (pinfunction "2_2") (pintype "passive"))
      (node (ref "D40") (pin "3") (pinfunction "3_3") (pintype "passive"))
      (node (ref "R247") (pin "1") (pinfunction "1_1") (pintype "passive"))
      (node (ref "U12") (pin "1") (pinfunction "~{{SD}}_1") (pintype "input"))
    )
    (net (code "134") (name "Net-(U17-CD)") (class "Default")
      (node (ref "C57") (pin "2") (pinfunction "2_2") (pintype "passive"))
      (node (ref "D12") (pin "3") (pinfunction "A_3") (pintype "passive"))
      (node (ref "U17") (pin "5") (pinfunction "CD_5") (pintype "input"))
    )
    (net (code "135") (name "Net-(U17-OUT)") (class "Default")
      (node (ref "U17") (pin "1") (pinfunction "OUT_1") (pintype "output"))
      (node (ref "U20") (pin "3") (pinfunction "3_3") (pintype "input"))
    )
    (net (code "136") (name "Net-(U18A-D)") (class "Default")
      (node (ref "U18") (pin "11") (pinfunction "C_11") (pintype "input"))
      (node (ref "U18") (pin "2") (pinfunction "D_2") (pintype "input"))
      (node (ref "U18") (pin "6") (pinfunction "~{{Q}}_6") (pintype "output"))
    )
    (net (code "137") (name "Net-(U18B-D)") (class "Default")
      (node (ref "R92") (pin "1") (pinfunction "1_1") (pintype "passive"))
      (node (ref "U18") (pin "12") (pinfunction "D_12") (pintype "input"))
      (node (ref "U18") (pin "8") (pinfunction "~{{Q}}_8") (pintype "output"))
    )
    (net (code "138") (name "Net-(U31-CD)") (class "Default")
      (node (ref "C100") (pin "1") (pinfunction "1_1") (pintype "passive"))
      (node (ref "D34") (pin "3") (pinfunction "A_3") (pintype "passive"))
      (node (ref "U31") (pin "5") (pinfunction "CD_5") (pintype "input"))
    )
    (net (code "139") (name "Net-(U31-VDD)") (class "Default")
      (node (ref "C97") (pin "1") (pinfunction "1_1") (pintype "passive"))
      (node (ref "D34") (pin "1") (pinfunction "A_1") (pintype "passive"))
      (node (ref "R195") (pin "2") (pinfunction "2_2") (pintype "passive"))
      (node (ref "U31") (pin "2") (pinfunction "VDD_2") (pintype "power_in"))
    )
    (net (code "140") (name "Net-(U46-RB)") (class "Default")
      (node (ref "R75") (pin "2") (pinfunction "2_2") (pintype "passive"))
      (node (ref "U46") (pin "14") (pinfunction "RB_14") (pintype "output"))
    )
    (net (code "141") (name "Net-(U46-toBUFF)") (class "Default")
      (node (ref "R69") (pin "1") (pinfunction "1_1") (pintype "passive"))
      (node (ref "U46") (pin "2") (pinfunction "toBUFF_2") (pintype "output"))
    )
    (net (code "142") (name "Net-(U47B-+)") (class "Default")
      (node (ref "C158") (pin "2") (pinfunction "2_2") (pintype "passive"))
      (node (ref "R27") (pin "1") (pinfunction "1_1") (pintype "passive"))
      (node (ref "R33") (pin "1") (pinfunction "1_1") (pintype "passive"))
      (node (ref "U47") (pin "5") (pinfunction "+_5") (pintype "input"))
    )
    (net (code "143") (name "Net-(U49-A8)") (class "Default")
      (node (ref "R219") (pin "2") (pinfunction "2_2") (pintype "passive"))
      (node (ref "U49") (pin "11") (pinfunction "A8_11") (pintype "bidirectional"))
    )
    (net (code "144") (name "Net-(U49-B8)") (class "Default")
      (node (ref "R223") (pin "1") (pinfunction "1_1") (pintype "passive"))
      (node (ref "U49") (pin "14") (pinfunction "B8_14") (pintype "bidirectional"))
    )
    (net (code "145") (name "Net-(U49-DIR)") (class "Default")
      (node (ref "R364") (pin "2") (pinfunction "2_2") (pintype "passive"))
      (node (ref "R370") (pin "1") (pinfunction "1_1") (pintype "passive"))
      (node (ref "U49") (pin "2") (pinfunction "DIR_2") (pintype "input"))
    )
    (net (code "146") (name "Net-(U49-G#)") (class "Default")
      (node (ref "C270") (pin "2") (pinfunction "2_2") (pintype "passive"))
      (node (ref "D3") (pin "1") (pinfunction "A_1") (pintype "passive"))
      (node (ref "D3") (pin "3") (pinfunction "A_3") (pintype "passive"))
      (node (ref "R258") (pin "2") (pinfunction "2_2") (pintype "passive"))
      (node (ref "U49") (pin "23") (pinfunction "G#_23") (pintype "input"))
    )
    (net (code "147") (name "Net-(U66-Pad1)") (class "Default")
      (node (ref "U66") (pin "1") (pinfunction "1_1") (pintype "output"))
      (node (ref "U66") (pin "8") (pinfunction "8_8") (pintype "input"))
    )
    (net (code "148") (name "Net-(U66-Pad4)") (class "Default")
      (node (ref "U66") (pin "4") (pinfunction "4_4") (pintype "output"))
      (node (ref "U66") (pin "9") (pinfunction "9_9") (pintype "input"))
    )
    (net (code "149") (name "PNET1") (class "Default")
      (node (ref "C208") (pin "2") (pinfunction "2_2") (pintype "passive"))
      (node (ref "C211") (pin "2") (pinfunction "2_2") (pintype "passive"))
      (node (ref "C212") (pin "1") (pinfunction "1_1") (pintype "passive"))
      (node (ref "C215") (pin "1") (pinfunction "1_1") (pintype "passive"))
      (node (ref "R120") (pin "1") (pinfunction "1_1") (pintype "passive"))
      (node (ref "R258") (pin "1") (pinfunction "1_1") (pintype "passive"))
      (node (ref "U49") (pin "1") (pinfunction "VCCA_1") (pintype "power_in"))
      (node (ref "U64") (pin "13") (pinfunction "13_13") (pintype "input"))
    )
    (net (code "150") (name "PNET2") (class "Default")
      (node (ref "C203") (pin "2") (pinfunction "2_2") (pintype "passive"))
      (node (ref "C204") (pin "2") (pinfunction "2_2") (pintype "passive"))
      (node (ref "C205") (pin "1") (pinfunction "1_1") (pintype "passive"))
      (node (ref "C68") (pin "1") (pinfunction "1_1") (pintype "passive"))
      (node (ref "D34") (pin "2") (pinfunction "K_2") (pintype "passive"))
      (node (ref "R195") (pin "1") (pinfunction "1_1") (pintype "passive"))
      (node (ref "R243") (pin "1") (pinfunction "1_1") (pintype "passive"))
      (node (ref "R244") (pin "1") (pinfunction "1_1") (pintype "passive"))
      (node (ref "R245") (pin "1") (pinfunction "1_1") (pintype "passive"))
      (node (ref "R256") (pin "2") (pinfunction "2_2") (pintype "passive"))
      (node (ref "R28") (pin "2") (pinfunction "2_2") (pintype "passive"))
      (node (ref "U10") (pin "1") (pinfunction "VCC_1") (pintype "power_in"))
      (node (ref "U12") (pin "6") (pinfunction "VDD_6") (pintype "power_in"))
      (node (ref "U18") (pin "1") (pinfunction "~{{R}}_1") (pintype "input"))
      (node (ref "U18") (pin "10") (pinfunction "~{{S}}_10") (pintype "input"))
      (node (ref "U18") (pin "13") (pinfunction "~{{R}}_13") (pintype "input"))
      (node (ref "U18") (pin "14") (pinfunction "VCC_14") (pintype "power_in"))
      (node (ref "U18") (pin "4") (pinfunction "~{{S}}_4") (pintype "input"))
    )
    (net (code "151") (name "PNET5") (class "Default")
      (node (ref "C19") (pin "2") (pinfunction "2_2") (pintype "passive"))
      (node (ref "D12") (pin "2") (pinfunction "K_2") (pintype "passive"))
      (node (ref "R226") (pin "2") (pinfunction "2_2") (pintype "passive"))
      (node (ref "R47") (pin "1") (pinfunction "1_1") (pintype "passive"))
      (node (ref "R48") (pin "2") (pinfunction "2_2") (pintype "passive"))
      (node (ref "R50") (pin "1") (pinfunction "1_1") (pintype "passive"))
      (node (ref "R54") (pin "1") (pinfunction "1_1") (pintype "passive"))
      (node (ref "R55") (pin "2") (pinfunction "2_2") (pintype "passive"))
      (node (ref "R56") (pin "2") (pinfunction "2_2") (pintype "passive"))
      (node (ref "R64") (pin "1") (pinfunction "1_1") (pintype "passive"))
      (node (ref "R65") (pin "1") (pinfunction "1_1") (pintype "passive"))
      (node (ref "R88") (pin "2") (pinfunction "2_2") (pintype "passive"))
      (node (ref "U34") (pin "14") (pinfunction "VCC_14") (pintype "power_in"))
      (node (ref "U4") (pin "20") (pinfunction "VCC_20") (pintype "power_in"))
      (node (ref "U4") (pin "27") (pinfunction "VCC_27") (pintype "power_in"))
    )
    (net (code "152") (name "PNET6") (class "Default")
      (node (ref "C14") (pin "1") (pinfunction "1_1") (pintype "passive"))
      (node (ref "C149") (pin "2") (pinfunction "2_2") (pintype "passive"))
      (node (ref "C151") (pin "1") (pinfunction "1_1") (pintype "passive"))
      (node (ref "C9") (pin "1") (pinfunction "1_1") (pintype "passive"))
      (node (ref "R222") (pin "1") (pinfunction "1_1") (pintype "passive"))
      (node (ref "R27") (pin "2") (pinfunction "2_2") (pintype "passive"))
      (node (ref "R28") (pin "1") (pinfunction "1_1") (pintype "passive"))
      (node (ref "R36") (pin "1") (pinfunction "1_1") (pintype "passive"))
      (node (ref "R37") (pin "1") (pinfunction "1_1") (pintype "passive"))
      (node (ref "U47") (pin "8") (pinfunction "V+_8") (pintype "power_in"))
      (node (ref "U48") (pin "8") (pinfunction "V+_8") (pintype "power_in"))
    )
    (net (code "153") (name "unconnected-(U4-GamePad-Pad13)") (class "Default")
      (node (ref "U4") (pin "13") (pinfunction "GamePad_13") (pintype "input+no_connect"))
    )
    (net (code "154") (name "unconnected-(U4-NC-Pad3)") (class "Default")
      (node (ref "U4") (pin "3") (pinfunction "NC_3") (pintype "input"))
    )
    (net (code "155") (name "unconnected-(U4-NC-Pad12)") (class "Default")
      (node (ref "U4") (pin "12") (pinfunction "NC_12") (pintype "input"))
    )
    (net (code "156") (name "unconnected-(U4-NC-Pad15)") (class "Default")
      (node (ref "U4") (pin "15") (pinfunction "NC_15") (pintype "input"))
    )
    (net (code "157") (name "unconnected-(U4-NC-Pad17)") (class "Default")
      (node (ref "U4") (pin "17") (pinfunction "NC_17") (pintype "input"))
    )
    (net (code "158") (name "unconnected-(U4-NC-Pad19)") (class "Default")
      (node (ref "U4") (pin "19") (pinfunction "NC_19") (pintype "input"))
    )
    (net (code "159") (name "unconnected-(U10-IRQ#-Pad2)") (class "Default")
      (node (ref "U10") (pin "2") (pinfunction "IRQ#_2") (pintype "output+no_connect"))
    )
    (net (code "160") (name "unconnected-(U10-NC-Pad8)") (class "Default")
      (node (ref "U10") (pin "8") (pinfunction "NC_8") (pintype "input"))
    )
    (net (code "161") (name "unconnected-(U10-NC-Pad9)") (class "Default")
      (node (ref "U10") (pin "9") (pinfunction "NC_9") (pintype "input"))
    )
    (net (code "162") (name "unconnected-(U10-NC-Pad19)") (class "Default")
      (node (ref "U10") (pin "19") (pinfunction "NC_19") (pintype "input"))
    )
    (net (code "163") (name "unconnected-(U10-NC-Pad22)") (class "Default")
      (node (ref "U10") (pin "22") (pinfunction "NC_22") (pintype "input"))
    )
    (net (code "164") (name "unconnected-(U17-NC-Pad4)") (class "Default")
      (node (ref "U17") (pin "4") (pinfunction "NC_4") (pintype "input"))
    )
    (net (code "165") (name "unconnected-(U18A-Q-Pad5)") (class "Default")
      (node (ref "U18") (pin "5") (pinfunction "Q_5") (pintype "output+no_connect"))
    )
    (net (code "166") (name "unconnected-(U18B-Q-Pad9)") (class "Default")
      (node (ref "U18") (pin "9") (pinfunction "Q_9") (pintype "output+no_connect"))
    )
    (net (code "167") (name "unconnected-(U31-NC-Pad4)") (class "Default")
      (node (ref "U31") (pin "4") (pinfunction "NC_4") (pintype "input"))
    )
    (net (code "168") (name "unconnected-(U46-NC-Pad3)") (class "Default")
      (node (ref "U46") (pin "3") (pinfunction "NC_3") (pintype "input"))
    )
    (net (code "169") (name "unconnected-(U46-NC-Pad5)") (class "Default")
      (node (ref "U46") (pin "5") (pinfunction "NC_5") (pintype "input"))
    )
    (net (code "170") (name "unconnected-(U46-NC-Pad6)") (class "Default")
      (node (ref "U46") (pin "6") (pinfunction "NC_6") (pintype "input"))
    )
    (net (code "171") (name "unconnected-(U46-NC-Pad8)") (class "Default")
      (node (ref "U46") (pin "8") (pinfunction "NC_8") (pintype "input"))
    )
    (net (code "172") (name "unconnected-(U46-NC-Pad9)") (class "Default")
      (node (ref "U46") (pin "9") (pinfunction "NC_9") (pintype "input"))
    )
    (net (code "173") (name "unconnected-(U46-NC-Pad11)") (class "Default")
      (node (ref "U46") (pin "11") (pinfunction "NC_11") (pintype "input"))
    )
    (net (code "174") (name "unconnected-(U46-NC-Pad13)") (class "Default")
      (node (ref "U46") (pin "13") (pinfunction "NC_13") (pintype "input"))
    )
    (net (code "175") (name "unconnected-(U46-NC-Pad15)") (class "Default")
      (node (ref "U46") (pin "15") (pinfunction "NC_15") (pintype "input"))
    )
    (net (code "176") (name "unconnected-(U48-D-Pad3)") (class "Default")
      (node (ref "U48") (pin "3") (pinfunction "D_3") (pintype "input+no_connect"))
    )
  )
)
